# D5035-03.net
KiCad netlist of a schematic drawn in Altium Designer
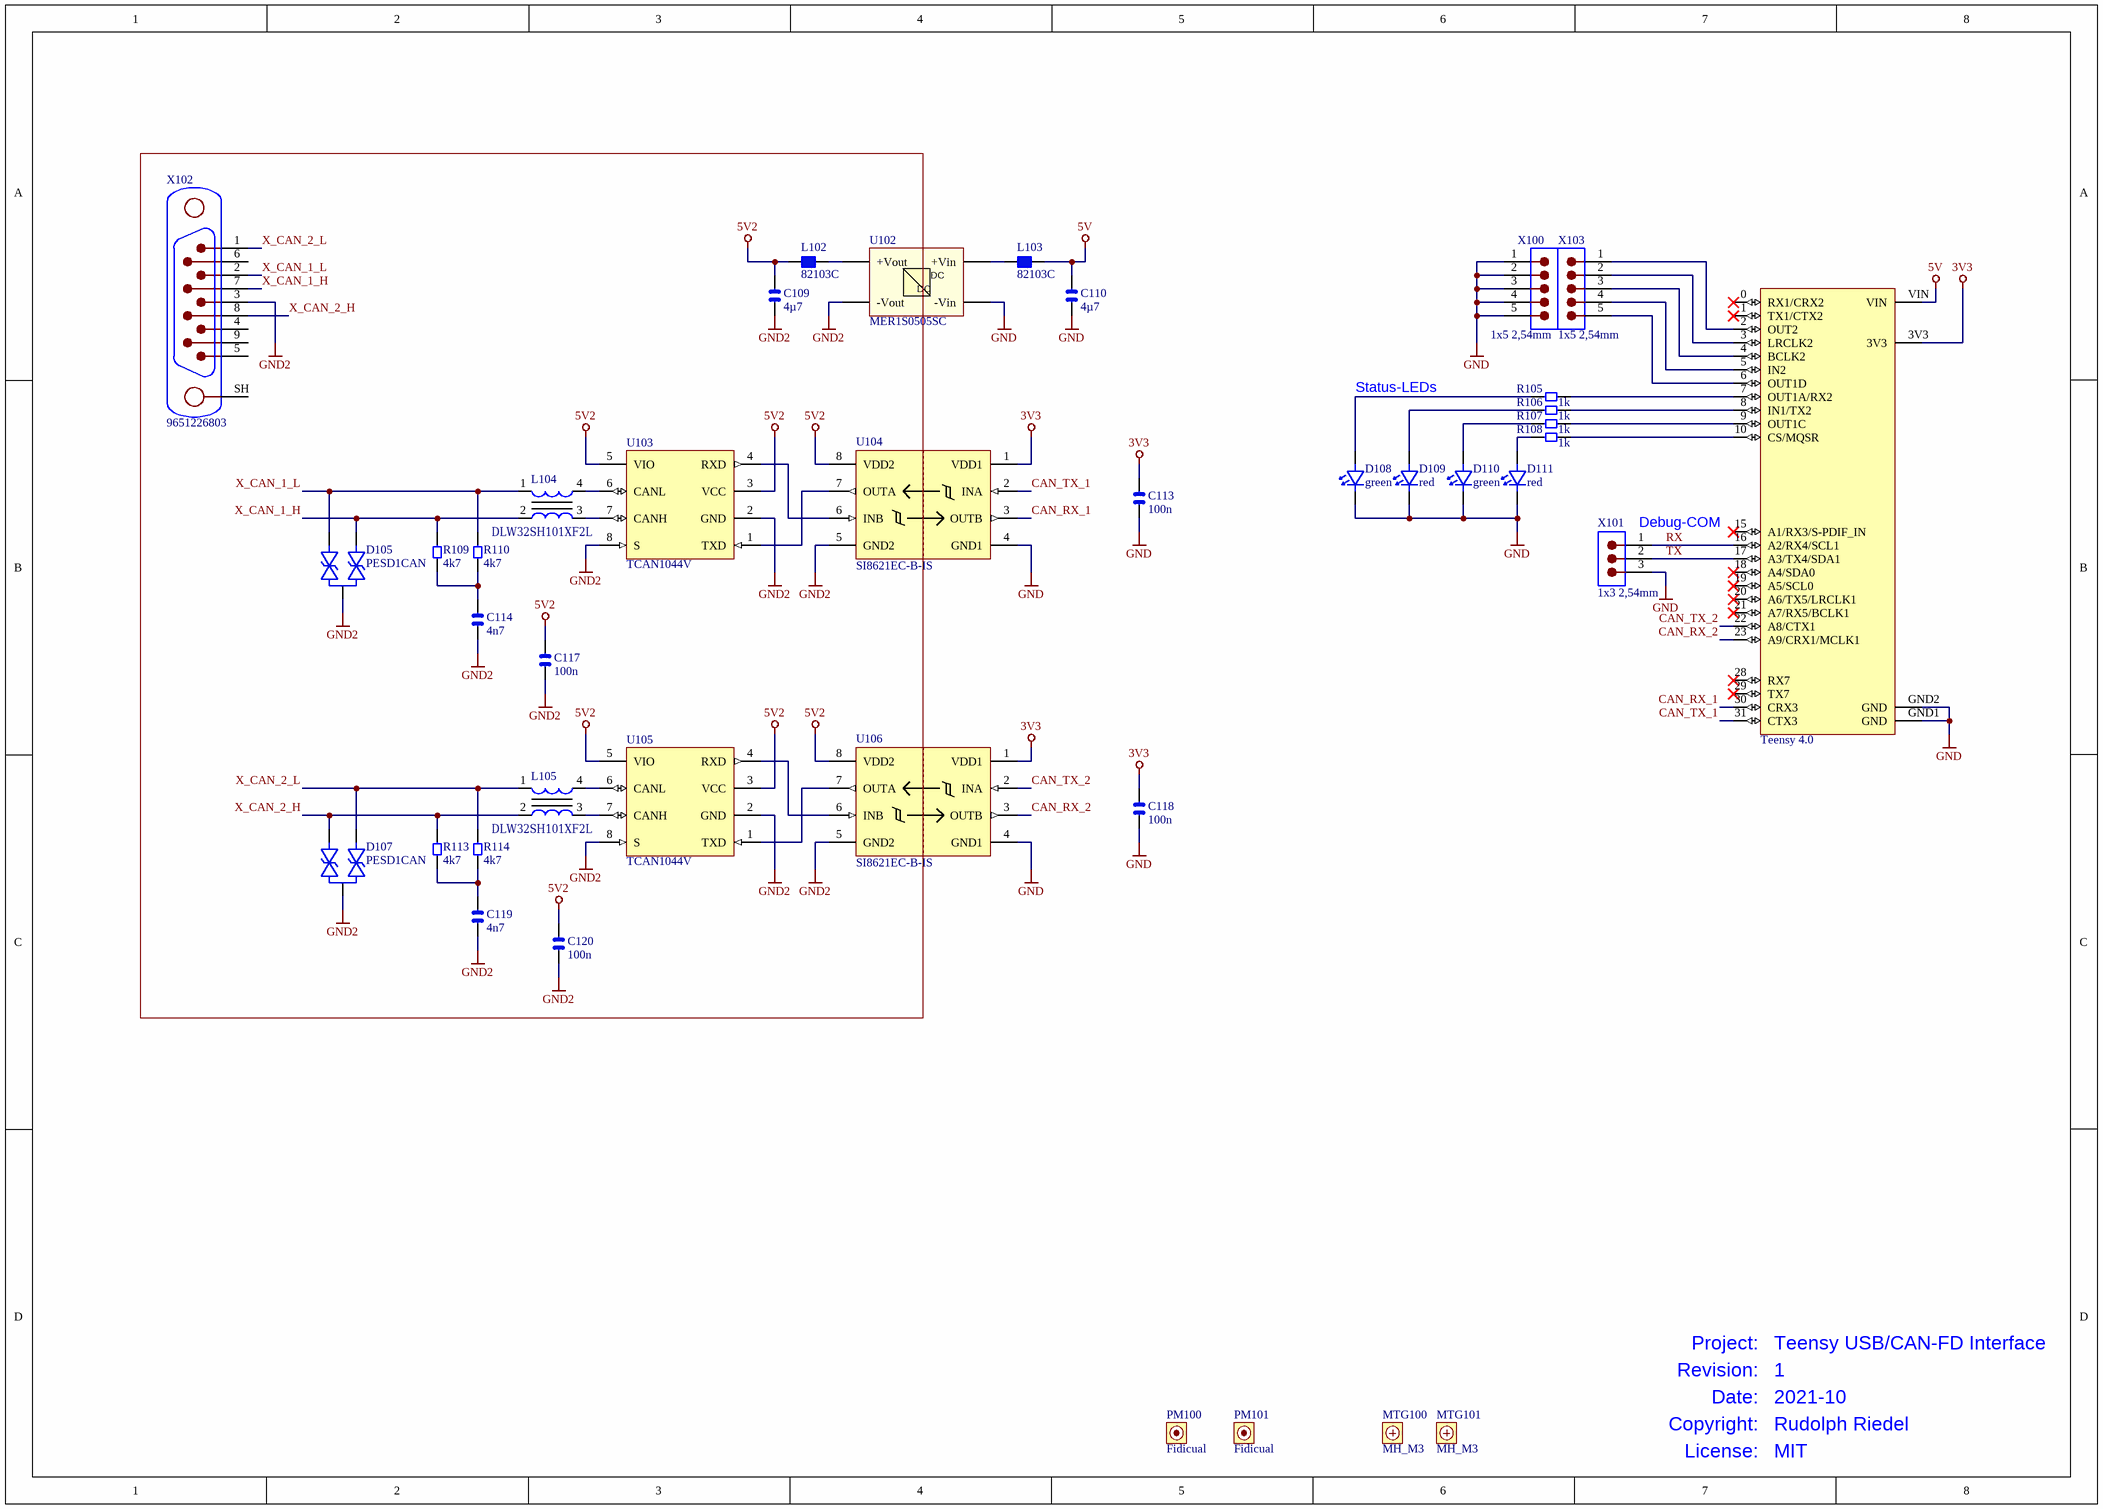
[diagram p0: D5035-03.SchDoc]

(export (version "E")
  (design (tool "Eeschema 10.0.6"))
  (components
    (comp (ref "C109")
      (value "4µ7")
      (footprint "CAPC2012X14L")
      (description "0805 Chip Capacitor")
      (fields (field (name "PART NUMBER") "CAPC_0805") (field (name "EDITOR") "rriedel"))
      (libsource (lib "HW-Labor_GF") (part "CAP_2_V2"))
    )
    (comp (ref "C110")
      (value "4µ7")
      (footprint "CAPC2012X14L")
      (description "0805 Chip Capacitor")
      (fields (field (name "PART NUMBER") "CAPC_0805") (field (name "EDITOR") "rriedel"))
      (libsource (lib "HW-Labor_GF") (part "CAP_2_V2"))
    )
    (comp (ref "C113")
      (value "100n")
      (footprint "CAPC1608X09L")
      (description "0603 Chip Capacitor")
      (fields (field (name "PART NUMBER") "CAPC_0603") (field (name "EDITOR") "rriedel"))
      (libsource (lib "HW-Labor_GF") (part "CAP_2_V2"))
    )
    (comp (ref "C114")
      (value "4n7")
      (footprint "CAPC2012X14L")
      (description "0805 Chip Capacitor")
      (fields (field (name "PART NUMBER") "CAPC_0805") (field (name "EDITOR") "rriedel"))
      (libsource (lib "HW-Labor_GF") (part "CAP_2_V2"))
    )
    (comp (ref "C117")
      (value "100n")
      (footprint "CAPC1608X09L")
      (description "0603 Chip Capacitor")
      (fields (field (name "PART NUMBER") "CAPC_0603") (field (name "EDITOR") "rriedel"))
      (libsource (lib "HW-Labor_GF") (part "CAP_2_V2"))
    )
    (comp (ref "C118")
      (value "100n")
      (footprint "CAPC1608X09L")
      (description "0603 Chip Capacitor")
      (fields (field (name "PART NUMBER") "CAPC_0603") (field (name "EDITOR") "rriedel"))
      (libsource (lib "HW-Labor_GF") (part "CAP_2_V2"))
    )
    (comp (ref "C119")
      (value "4n7")
      (footprint "CAPC2012X14L")
      (description "0805 Chip Capacitor")
      (fields (field (name "PART NUMBER") "CAPC_0805") (field (name "EDITOR") "rriedel"))
      (libsource (lib "HW-Labor_GF") (part "CAP_2_V2"))
    )
    (comp (ref "C120")
      (value "100n")
      (footprint "CAPC1608X09L")
      (description "0603 Chip Capacitor")
      (fields (field (name "PART NUMBER") "CAPC_0603") (field (name "EDITOR") "rriedel"))
      (libsource (lib "HW-Labor_GF") (part "CAP_2_V2"))
    )
    (comp (ref "D105")
      (value "PESD1CAN")
      (footprint "SOT95P280X110-3N")
      (description "CAN bus ESD protection diode")
      (fields
        (field (name "MANUFACTURER") "Nexperia")
        (field (name "DISTRIBUTOR_1_PART_NUMBER") "1727-3817-1-ND")
        (field (name "EDITOR") "rriedel")
      )
      (libsource (lib "HW-Labor_GF") (part "PESD1CAN"))
    )
    (comp (ref "D107")
      (value "PESD1CAN")
      (footprint "SOT95P280X110-3N")
      (description "CAN bus ESD protection diode")
      (fields
        (field (name "MANUFACTURER") "Nexperia")
        (field (name "DISTRIBUTOR_1_PART_NUMBER") "1727-3817-1-ND")
        (field (name "EDITOR") "rriedel")
      )
      (libsource (lib "HW-Labor_GF") (part "PESD1CAN"))
    )
    (comp (ref "D108")
      (value "green")
      (footprint "DIOC1608X06N_LED")
      (description "LED, 0603")
      (fields (field (name "PART NUMBER") "LED_0603") (field (name "EDITOR") "rriedel"))
      (libsource (lib "HW-Labor_GF") (part "LED_generic"))
    )
    (comp (ref "D109")
      (value "red")
      (footprint "DIOC1608X06N_LED")
      (description "LED, 0603")
      (fields (field (name "PART NUMBER") "LED_0603") (field (name "EDITOR") "rriedel"))
      (libsource (lib "HW-Labor_GF") (part "LED_generic"))
    )
    (comp (ref "D110")
      (value "green")
      (footprint "DIOC1608X06N_LED")
      (description "LED, 0603")
      (fields (field (name "PART NUMBER") "LED_0603") (field (name "EDITOR") "rriedel"))
      (libsource (lib "HW-Labor_GF") (part "LED_generic"))
    )
    (comp (ref "D111")
      (value "red")
      (footprint "DIOC1608X06N_LED")
      (description "LED, 0603")
      (fields (field (name "PART NUMBER") "LED_0603") (field (name "EDITOR") "rriedel"))
      (libsource (lib "HW-Labor_GF") (part "LED_generic"))
    )
    (comp (ref "L102")
      (value "82103C")
      (footprint "Murata_8200C")
      (description "10µH, 0,5A, 400mR")
      (fields
        (field (name "MANUFACTURER") "Murata")
        (field (name "DISTRIBUTOR_1_PART_NUMBER") "811-2473-1-ND")
        (field (name "EDITOR") "rriedel")
      )
      (libsource (lib "HW-Labor_GF") (part "IND_2_V1"))
    )
    (comp (ref "L103")
      (value "82103C")
      (footprint "Murata_8200C")
      (description "10µH, 0,5A, 400mR")
      (fields
        (field (name "MANUFACTURER") "Murata")
        (field (name "DISTRIBUTOR_1_PART_NUMBER") "811-2473-1-ND")
        (field (name "EDITOR") "rriedel")
      )
      (libsource (lib "HW-Labor_GF") (part "IND_2_V1"))
    )
    (comp (ref "L104")
      (value "DLW32SH101XF2L‎")
      (footprint "ACT1210")
      (description "Common Mode Filter,  -50°C ... +150°C, AEC-Q200")
      (fields
        (field (name "PART NUMBER") "ACT1210-101-2P-TL00")
        (field (name "MANUFACTURER") "TDK")
        (field (name "EDITOR") "rriedel")
      )
      (libsource (lib "HW-Labor_GF") (part "CAN_DROSSEL"))
    )
    (comp (ref "L105")
      (value "DLW32SH101XF2L‎")
      (footprint "ACT1210")
      (description "Common Mode Filter,  -50°C ... +150°C, AEC-Q200")
      (fields
        (field (name "PART NUMBER") "ACT1210-101-2P-TL00")
        (field (name "MANUFACTURER") "TDK")
        (field (name "EDITOR") "rriedel")
      )
      (libsource (lib "HW-Labor_GF") (part "CAN_DROSSEL"))
    )
    (comp (ref "MTG100")
      (value "MH_M3")
      (footprint "HOLE_3_2MM")
      (description "Mounting-Hole for M3 screws")
      (fields (field (name "EDITOR") "rriedel"))
      (libsource (lib "HW-Labor_GF") (part "MTG_V1"))
    )
    (comp (ref "MTG101")
      (value "MH_M3")
      (footprint "HOLE_3_2MM")
      (description "Mounting-Hole for M3 screws")
      (fields (field (name "EDITOR") "rriedel"))
      (libsource (lib "HW-Labor_GF") (part "MTG_V1"))
    )
    (comp (ref "PM100")
      (value "Fidicual")
      (footprint "PM100")
      (fields (field (name "PART NUMBER") "PM100") (field (name "EDITOR") "rriedel"))
      (libsource (lib "HW-Labor_GF") (part "PM100"))
    )
    (comp (ref "PM101")
      (value "Fidicual")
      (footprint "PM100")
      (fields (field (name "PART NUMBER") "PM100") (field (name "EDITOR") "rriedel"))
      (libsource (lib "HW-Labor_GF") (part "PM100"))
    )
    (comp (ref "R105")
      (value "1k")
      (footprint "RESC1608X06L")
      (description "0603 Chip Resistor")
      (fields (field (name "PART NUMBER") "RESC_0603") (field (name "EDITOR") "rriedel"))
      (libsource (lib "HW-Labor_GF") (part "RES_2_V2"))
    )
    (comp (ref "R106")
      (value "1k")
      (footprint "RESC1608X06L")
      (description "0603 Chip Resistor")
      (fields (field (name "PART NUMBER") "RESC_0603") (field (name "EDITOR") "rriedel"))
      (libsource (lib "HW-Labor_GF") (part "RES_2_V2"))
    )
    (comp (ref "R107")
      (value "1k")
      (footprint "RESC1608X06L")
      (description "0603 Chip Resistor")
      (fields (field (name "PART NUMBER") "RESC_0603") (field (name "EDITOR") "rriedel"))
      (libsource (lib "HW-Labor_GF") (part "RES_2_V2"))
    )
    (comp (ref "R108")
      (value "1k")
      (footprint "RESC1608X06L")
      (description "0603 Chip Resistor")
      (fields (field (name "PART NUMBER") "RESC_0603") (field (name "EDITOR") "rriedel"))
      (libsource (lib "HW-Labor_GF") (part "RES_2_V2"))
    )
    (comp (ref "R109")
      (value "4k7")
      (footprint "RESC2012X06L")
      (description "0805 Chip Resistor")
      (fields (field (name "PART NUMBER") "RESC_0805") (field (name "EDITOR") "rriedel"))
      (libsource (lib "HW-Labor_GF") (part "RES_2_V2"))
    )
    (comp (ref "R110")
      (value "4k7")
      (footprint "RESC2012X06L")
      (description "0805 Chip Resistor")
      (fields (field (name "PART NUMBER") "RESC_0805") (field (name "EDITOR") "rriedel"))
      (libsource (lib "HW-Labor_GF") (part "RES_2_V2"))
    )
    (comp (ref "R113")
      (value "4k7")
      (footprint "RESC2012X06L")
      (description "0805 Chip Resistor")
      (fields (field (name "PART NUMBER") "RESC_0805") (field (name "EDITOR") "rriedel"))
      (libsource (lib "HW-Labor_GF") (part "RES_2_V2"))
    )
    (comp (ref "R114")
      (value "4k7")
      (footprint "RESC2012X06L")
      (description "0805 Chip Resistor")
      (fields (field (name "PART NUMBER") "RESC_0805") (field (name "EDITOR") "rriedel"))
      (libsource (lib "HW-Labor_GF") (part "RES_2_V2"))
    )
    (comp (ref "Teensy 4.0")
      (value "Teensy_4_0_minimal")
      (footprint "Teensy_4_0_minimal")
      (libsource (lib "Teensy4") (part "Teensy_4_0_minimal"))
    )
    (comp (ref "U102")
      (value "MER1S0505SC")
      (footprint "MER1SxxxxC")
      (description "Isolated 1W Single Output DC-DC Converters 5V/5V 200mA")
      (fields
        (field (name "MANUFACTURER") "Murata")
        (field (name "DISTRIBUTOR_1_PART_NUMBER") "811-2124-5-ND‎")
        (field (name "EDITOR") "rriedel")
      )
      (libsource (lib "HW-Labor_GF") (part "MER1SxxxxC"))
    )
    (comp (ref "U103")
      (value "TCAN1044V")
      (footprint "SOT65P280X100-8N")
      (description "CAN-FD transceiver 8MBit, VIO Pin")
      (fields
        (field (name "MANUFACTURER") "TI")
        (field (name "DISTRIBUTOR_1_PART_NUMBER") "296-TCAN1044VDDFRCT-ND")
        (field (name "EDITOR") "rriedel")
      )
      (libsource (lib "HW-Labor_GF") (part "TJA1051T_3"))
    )
    (comp (ref "U104")
      (value "SI8621EC-B-IS")
      (footprint "SOIC127P600X175-8N")
      (description "Dual channel digital isolator, 150Mbit, 3,75kV")
      (fields
        (field (name "MANUFACTURER") "Silicon Labs")
        (field (name "DISTRIBUTOR_1_PART_NUMBER") "336-4776-1-ND")
        (field (name "EDITOR") "rriedel")
      )
      (libsource (lib "HW-Labor_GF") (part "SI8621"))
    )
    (comp (ref "U105")
      (value "TCAN1044V")
      (footprint "SOT65P280X100-8N")
      (description "CAN-FD transceiver 8MBit, VIO Pin")
      (fields
        (field (name "MANUFACTURER") "TI")
        (field (name "DISTRIBUTOR_1_PART_NUMBER") "296-TCAN1044VDDFRCT-ND")
        (field (name "EDITOR") "rriedel")
      )
      (libsource (lib "HW-Labor_GF") (part "TJA1051T_3"))
    )
    (comp (ref "U106")
      (value "SI8621EC-B-IS")
      (footprint "SOIC127P600X175-8N")
      (description "Dual channel digital isolator, 150Mbit, 3,75kV")
      (fields
        (field (name "MANUFACTURER") "Silicon Labs")
        (field (name "DISTRIBUTOR_1_PART_NUMBER") "336-4776-1-ND")
        (field (name "EDITOR") "rriedel")
      )
      (libsource (lib "HW-Labor_GF") (part "SI8621"))
    )
    (comp (ref "X100")
      (value "1x5 2,54mm")
      (footprint "PAD_1x05_2_54mm")
      (description "Pin-Header 2,54 mm 5pins")
      (fields (field (name "PART NUMBER") "PINH_1x5_2_54") (field (name "EDITOR") "rriedel"))
      (libsource (lib "HW-Labor_GF") (part "CONM_1x5_V2"))
    )
    (comp (ref "X101")
      (value "1x3 2,54mm")
      (footprint "PINH_1x03_2_54mm")
      (description "Pin-Header 2,54 mm 3pins")
      (fields (field (name "PART NUMBER") "PINH_1x3_2_54") (field (name "EDITOR") "rriedel"))
      (libsource (lib "HW-Labor_GF") (part "CONM_1x3_V2"))
    )
    (comp (ref "X102")
      (value "9651226803")
      (footprint "09651226803")
      (description "D-Sub, 9 pin, male, right angle")
      (fields
        (field (name "MANUFACTURER") "Harting")
        (field (name "DISTRIBUTOR_1_PART_NUMBER") "2752007")
        (field (name "EDITOR") "rriedel")
      )
      (libsource (lib "HW-Labor_GF") (part "D_Sub_9_Male"))
    )
    (comp (ref "X103")
      (value "1x5 2,54mm")
      (footprint "PAD_1x05_2_54mm")
      (description "Pin-Header 2,54 mm 5pins")
      (fields (field (name "PART NUMBER") "PINH_1x5_2_54") (field (name "EDITOR") "rriedel"))
      (libsource (lib "HW-Labor_GF") (part "CONM_1x5_V2"))
    )
  )
  (nets
    (net (code "1") (name "/CAN_RX_1") (class "Default")
      (node (ref "Teensy 4.0") (pin "30") (pinfunction "CRX3_30") (pintype "bidirectional"))
      (node (ref "U104") (pin "3") (pinfunction "OUTB_3") (pintype "output"))
    )
    (net (code "2") (name "/CAN_RX_2") (class "Default")
      (node (ref "Teensy 4.0") (pin "23") (pinfunction "A9/CRX1/MCLK1_23") (pintype "bidirectional"))
      (node (ref "U106") (pin "3") (pinfunction "OUTB_3") (pintype "output"))
    )
    (net (code "3") (name "/CAN_TX_1") (class "Default")
      (node (ref "Teensy 4.0") (pin "31") (pinfunction "CTX3_31") (pintype "bidirectional"))
      (node (ref "U104") (pin "2") (pinfunction "INA_2") (pintype "input"))
    )
    (net (code "4") (name "/CAN_TX_2") (class "Default")
      (node (ref "Teensy 4.0") (pin "22") (pinfunction "A8/CTX1_22") (pintype "bidirectional"))
      (node (ref "U106") (pin "2") (pinfunction "INA_2") (pintype "input"))
    )
    (net (code "5") (name "/RX") (class "Default")
      (node (ref "Teensy 4.0") (pin "16") (pinfunction "A2/RX4/SCL1_16") (pintype "bidirectional"))
      (node (ref "X101") (pin "1") (pinfunction "1_1") (pintype "passive"))
    )
    (net (code "6") (name "/TX") (class "Default")
      (node (ref "Teensy 4.0") (pin "17") (pinfunction "A3/TX4/SDA1_17") (pintype "bidirectional"))
      (node (ref "X101") (pin "2") (pinfunction "2_2") (pintype "passive"))
    )
    (net (code "7") (name "/X_CAN_1_H") (class "Default")
      (node (ref "D105") (pin "2") (pinfunction "2_2") (pintype "passive"))
      (node (ref "L104") (pin "2") (pintype "passive"))
      (node (ref "R109") (pin "2") (pinfunction "2_2") (pintype "passive"))
      (node (ref "X102") (pin "7") (pinfunction "7_7") (pintype "passive"))
    )
    (net (code "8") (name "/X_CAN_1_L") (class "Default")
      (node (ref "D105") (pin "1") (pinfunction "1_1") (pintype "passive"))
      (node (ref "L104") (pin "1") (pintype "passive"))
      (node (ref "R110") (pin "2") (pinfunction "2_2") (pintype "passive"))
      (node (ref "X102") (pin "2") (pinfunction "2_2") (pintype "passive"))
    )
    (net (code "9") (name "/X_CAN_2_H") (class "Default")
      (node (ref "D107") (pin "1") (pinfunction "1_1") (pintype "passive"))
      (node (ref "L105") (pin "2") (pintype "passive"))
      (node (ref "R113") (pin "2") (pinfunction "2_2") (pintype "passive"))
      (node (ref "X102") (pin "8") (pinfunction "8_8") (pintype "passive"))
    )
    (net (code "10") (name "/X_CAN_2_L") (class "Default")
      (node (ref "D107") (pin "2") (pinfunction "2_2") (pintype "passive"))
      (node (ref "L105") (pin "1") (pintype "passive"))
      (node (ref "R114") (pin "2") (pinfunction "2_2") (pintype "passive"))
      (node (ref "X102") (pin "1") (pinfunction "1_1") (pintype "passive"))
    )
    (net (code "11") (name "3V3") (class "Default")
      (node (ref "C113") (pin "2") (pinfunction "2_2") (pintype "passive"))
      (node (ref "C118") (pin "2") (pinfunction "2_2") (pintype "passive"))
      (node (ref "Teensy 4.0") (pin "3V3") (pinfunction "3V3_3V3") (pintype "power_in"))
      (node (ref "U104") (pin "1") (pinfunction "VDD1_1") (pintype "power_in"))
      (node (ref "U106") (pin "1") (pinfunction "VDD1_1") (pintype "power_in"))
    )
    (net (code "12") (name "5V") (class "Default")
      (node (ref "C110") (pin "2") (pinfunction "2_2") (pintype "passive"))
      (node (ref "L103") (pin "1") (pinfunction "1_1") (pintype "passive"))
      (node (ref "Teensy 4.0") (pin "VIN") (pinfunction "VIN_VIN") (pintype "power_in"))
    )
    (net (code "13") (name "5V2") (class "Default")
      (node (ref "C109") (pin "2") (pinfunction "2_2") (pintype "passive"))
      (node (ref "C117") (pin "2") (pinfunction "2_2") (pintype "passive"))
      (node (ref "C120") (pin "2") (pinfunction "2_2") (pintype "passive"))
      (node (ref "L102") (pin "2") (pinfunction "2_2") (pintype "passive"))
      (node (ref "U103") (pin "3") (pinfunction "VCC_3") (pintype "power_in"))
      (node (ref "U103") (pin "5") (pinfunction "VIO_5") (pintype "power_in"))
      (node (ref "U104") (pin "8") (pinfunction "VDD2_8") (pintype "power_in"))
      (node (ref "U105") (pin "3") (pinfunction "VCC_3") (pintype "power_in"))
      (node (ref "U105") (pin "5") (pinfunction "VIO_5") (pintype "power_in"))
      (node (ref "U106") (pin "8") (pinfunction "VDD2_8") (pintype "power_in"))
    )
    (net (code "14") (name "GND") (class "Default")
      (node (ref "C110") (pin "1") (pinfunction "1_1") (pintype "passive"))
      (node (ref "C113") (pin "1") (pinfunction "1_1") (pintype "passive"))
      (node (ref "C118") (pin "1") (pinfunction "1_1") (pintype "passive"))
      (node (ref "D108") (pin "1") (pinfunction "1_1") (pintype "passive"))
      (node (ref "D109") (pin "1") (pinfunction "1_1") (pintype "passive"))
      (node (ref "D110") (pin "1") (pinfunction "1_1") (pintype "passive"))
      (node (ref "D111") (pin "1") (pinfunction "1_1") (pintype "passive"))
      (node (ref "Teensy 4.0") (pin "GND1") (pinfunction "GND_GND1") (pintype "power_in"))
      (node (ref "Teensy 4.0") (pin "GND2") (pinfunction "GND_GND2") (pintype "power_in"))
      (node (ref "U102") (pin "2") (pinfunction "-Vin_2") (pintype "power_in"))
      (node (ref "U104") (pin "4") (pinfunction "GND1_4") (pintype "power_in"))
      (node (ref "U106") (pin "4") (pinfunction "GND1_4") (pintype "power_in"))
      (node (ref "X100") (pin "1") (pinfunction "1_1") (pintype "passive"))
      (node (ref "X100") (pin "2") (pinfunction "2_2") (pintype "passive"))
      (node (ref "X100") (pin "3") (pinfunction "3_3") (pintype "passive"))
      (node (ref "X100") (pin "4") (pinfunction "4_4") (pintype "passive"))
      (node (ref "X100") (pin "5") (pinfunction "5_5") (pintype "passive"))
      (node (ref "X101") (pin "3") (pinfunction "3_3") (pintype "passive"))
    )
    (net (code "15") (name "GND2") (class "Default")
      (node (ref "C109") (pin "1") (pinfunction "1_1") (pintype "passive"))
      (node (ref "C114") (pin "1") (pinfunction "1_1") (pintype "passive"))
      (node (ref "C117") (pin "1") (pinfunction "1_1") (pintype "passive"))
      (node (ref "C119") (pin "1") (pinfunction "1_1") (pintype "passive"))
      (node (ref "C120") (pin "1") (pinfunction "1_1") (pintype "passive"))
      (node (ref "D105") (pin "3") (pinfunction "3_3") (pintype "passive"))
      (node (ref "D107") (pin "3") (pinfunction "3_3") (pintype "passive"))
      (node (ref "U102") (pin "4") (pinfunction "-Vout_4") (pintype "power_in"))
      (node (ref "U103") (pin "2") (pinfunction "GND_2") (pintype "power_in"))
      (node (ref "U103") (pin "8") (pinfunction "S_8") (pintype "input"))
      (node (ref "U104") (pin "5") (pinfunction "GND2_5") (pintype "power_in"))
      (node (ref "U105") (pin "2") (pinfunction "GND_2") (pintype "power_in"))
      (node (ref "U105") (pin "8") (pinfunction "S_8") (pintype "input"))
      (node (ref "U106") (pin "5") (pinfunction "GND2_5") (pintype "power_in"))
      (node (ref "X102") (pin "3") (pinfunction "3_3") (pintype "passive"))
    )
    (net (code "16") (name "Net-(C114-Pad2)") (class "Default")
      (node (ref "C114") (pin "2") (pinfunction "2_2") (pintype "passive"))
      (node (ref "R109") (pin "1") (pinfunction "1_1") (pintype "passive"))
      (node (ref "R110") (pin "1") (pinfunction "1_1") (pintype "passive"))
    )
    (net (code "17") (name "Net-(C119-Pad2)") (class "Default")
      (node (ref "C119") (pin "2") (pinfunction "2_2") (pintype "passive"))
      (node (ref "R113") (pin "1") (pinfunction "1_1") (pintype "passive"))
      (node (ref "R114") (pin "1") (pinfunction "1_1") (pintype "passive"))
    )
    (net (code "18") (name "Net-(D108-Pad2)") (class "Default")
      (node (ref "D108") (pin "2") (pinfunction "2_2") (pintype "passive"))
      (node (ref "R105") (pin "1") (pinfunction "1_1") (pintype "passive"))
    )
    (net (code "19") (name "Net-(D109-Pad2)") (class "Default")
      (node (ref "D109") (pin "2") (pinfunction "2_2") (pintype "passive"))
      (node (ref "R106") (pin "1") (pinfunction "1_1") (pintype "passive"))
    )
    (net (code "20") (name "Net-(D110-Pad2)") (class "Default")
      (node (ref "D110") (pin "2") (pinfunction "2_2") (pintype "passive"))
      (node (ref "R107") (pin "1") (pinfunction "1_1") (pintype "passive"))
    )
    (net (code "21") (name "Net-(D111-Pad2)") (class "Default")
      (node (ref "D111") (pin "2") (pinfunction "2_2") (pintype "passive"))
      (node (ref "R108") (pin "1") (pinfunction "1_1") (pintype "passive"))
    )
    (net (code "22") (name "Net-(Teensy 4.0-BCLK2)") (class "Default")
      (node (ref "Teensy 4.0") (pin "4") (pinfunction "BCLK2_4") (pintype "bidirectional"))
      (node (ref "X103") (pin "3") (pinfunction "3_3") (pintype "passive"))
    )
    (net (code "23") (name "Net-(Teensy 4.0-CS{slash}MQSR)") (class "Default")
      (node (ref "R108") (pin "2") (pinfunction "2_2") (pintype "passive"))
      (node (ref "Teensy 4.0") (pin "10") (pinfunction "CS/MQSR_10") (pintype "bidirectional"))
    )
    (net (code "24") (name "Net-(Teensy 4.0-IN1{slash}TX2)") (class "Default")
      (node (ref "R106") (pin "2") (pinfunction "2_2") (pintype "passive"))
      (node (ref "Teensy 4.0") (pin "8") (pinfunction "IN1/TX2_8") (pintype "bidirectional"))
    )
    (net (code "25") (name "Net-(Teensy 4.0-IN2)") (class "Default")
      (node (ref "Teensy 4.0") (pin "5") (pinfunction "IN2_5") (pintype "bidirectional"))
      (node (ref "X103") (pin "4") (pinfunction "4_4") (pintype "passive"))
    )
    (net (code "26") (name "Net-(Teensy 4.0-LRCLK2)") (class "Default")
      (node (ref "Teensy 4.0") (pin "3") (pinfunction "LRCLK2_3") (pintype "bidirectional"))
      (node (ref "X103") (pin "2") (pinfunction "2_2") (pintype "passive"))
    )
    (net (code "27") (name "Net-(Teensy 4.0-OUT1A{slash}RX2)") (class "Default")
      (node (ref "R105") (pin "2") (pinfunction "2_2") (pintype "passive"))
      (node (ref "Teensy 4.0") (pin "7") (pinfunction "OUT1A/RX2_7") (pintype "bidirectional"))
    )
    (net (code "28") (name "Net-(Teensy 4.0-OUT1C)") (class "Default")
      (node (ref "R107") (pin "2") (pinfunction "2_2") (pintype "passive"))
      (node (ref "Teensy 4.0") (pin "9") (pinfunction "OUT1C_9") (pintype "bidirectional"))
    )
    (net (code "29") (name "Net-(Teensy 4.0-OUT1D)") (class "Default")
      (node (ref "Teensy 4.0") (pin "6") (pinfunction "OUT1D_6") (pintype "bidirectional"))
      (node (ref "X103") (pin "5") (pinfunction "5_5") (pintype "passive"))
    )
    (net (code "30") (name "Net-(Teensy 4.0-OUT2)") (class "Default")
      (node (ref "Teensy 4.0") (pin "2") (pinfunction "OUT2_2") (pintype "bidirectional"))
      (node (ref "X103") (pin "1") (pinfunction "1_1") (pintype "passive"))
    )
    (net (code "31") (name "Net-(U102-+Vin)") (class "Default")
      (node (ref "L103") (pin "2") (pinfunction "2_2") (pintype "passive"))
      (node (ref "U102") (pin "1") (pinfunction "+Vin_1") (pintype "power_in"))
    )
    (net (code "32") (name "Net-(U102-+Vout)") (class "Default")
      (node (ref "L102") (pin "1") (pinfunction "1_1") (pintype "passive"))
      (node (ref "U102") (pin "6") (pinfunction "+Vout_6") (pintype "power_in"))
    )
    (net (code "33") (name "Net-(U103-CANH)") (class "Default")
      (node (ref "L104") (pin "3") (pintype "passive"))
      (node (ref "U103") (pin "7") (pinfunction "CANH_7") (pintype "bidirectional"))
    )
    (net (code "34") (name "Net-(U103-CANL)") (class "Default")
      (node (ref "L104") (pin "4") (pintype "passive"))
      (node (ref "U103") (pin "6") (pinfunction "CANL_6") (pintype "bidirectional"))
    )
    (net (code "35") (name "Net-(U103-RXD)") (class "Default")
      (node (ref "U103") (pin "4") (pinfunction "RXD_4") (pintype "output"))
      (node (ref "U104") (pin "6") (pinfunction "INB_6") (pintype "input"))
    )
    (net (code "36") (name "Net-(U103-TXD)") (class "Default")
      (node (ref "U103") (pin "1") (pinfunction "TXD_1") (pintype "input"))
      (node (ref "U104") (pin "7") (pinfunction "OUTA_7") (pintype "output"))
    )
    (net (code "37") (name "Net-(U105-CANH)") (class "Default")
      (node (ref "L105") (pin "3") (pintype "passive"))
      (node (ref "U105") (pin "7") (pinfunction "CANH_7") (pintype "bidirectional"))
    )
    (net (code "38") (name "Net-(U105-CANL)") (class "Default")
      (node (ref "L105") (pin "4") (pintype "passive"))
      (node (ref "U105") (pin "6") (pinfunction "CANL_6") (pintype "bidirectional"))
    )
    (net (code "39") (name "Net-(U105-RXD)") (class "Default")
      (node (ref "U105") (pin "4") (pinfunction "RXD_4") (pintype "output"))
      (node (ref "U106") (pin "6") (pinfunction "INB_6") (pintype "input"))
    )
    (net (code "40") (name "Net-(U105-TXD)") (class "Default")
      (node (ref "U105") (pin "1") (pinfunction "TXD_1") (pintype "input"))
      (node (ref "U106") (pin "7") (pinfunction "OUTA_7") (pintype "output"))
    )
    (net (code "41") (name "unconnected-(Teensy 4.0-A1{slash}RX3{slash}S-PDIF_IN-Pad15)") (class "Default")
      (node (ref "Teensy 4.0") (pin "15") (pinfunction "A1/RX3/S-PDIF_IN_15") (pintype "bidirectional+no_connect"))
    )
    (net (code "42") (name "unconnected-(Teensy 4.0-A4{slash}SDA0-Pad18)") (class "Default")
      (node (ref "Teensy 4.0") (pin "18") (pinfunction "A4/SDA0_18") (pintype "bidirectional+no_connect"))
    )
    (net (code "43") (name "unconnected-(Teensy 4.0-A5{slash}SCL0-Pad19)") (class "Default")
      (node (ref "Teensy 4.0") (pin "19") (pinfunction "A5/SCL0_19") (pintype "bidirectional+no_connect"))
    )
    (net (code "44") (name "unconnected-(Teensy 4.0-A6{slash}TX5{slash}LRCLK1-Pad20)") (class "Default")
      (node (ref "Teensy 4.0") (pin "20") (pinfunction "A6/TX5/LRCLK1_20") (pintype "bidirectional+no_connect"))
    )
    (net (code "45") (name "unconnected-(Teensy 4.0-A7{slash}RX5{slash}BCLK1-Pad21)") (class "Default")
      (node (ref "Teensy 4.0") (pin "21") (pinfunction "A7/RX5/BCLK1_21") (pintype "bidirectional+no_connect"))
    )
    (net (code "46") (name "unconnected-(Teensy 4.0-RX1{slash}CRX2-Pad0)") (class "Default")
      (node (ref "Teensy 4.0") (pin "0") (pinfunction "RX1/CRX2_0") (pintype "bidirectional+no_connect"))
    )
    (net (code "47") (name "unconnected-(Teensy 4.0-RX7-Pad28)") (class "Default")
      (node (ref "Teensy 4.0") (pin "28") (pinfunction "RX7_28") (pintype "bidirectional+no_connect"))
    )
    (net (code "48") (name "unconnected-(Teensy 4.0-TX1{slash}CTX2-Pad1)") (class "Default")
      (node (ref "Teensy 4.0") (pin "1") (pinfunction "TX1/CTX2_1") (pintype "bidirectional+no_connect"))
    )
    (net (code "49") (name "unconnected-(Teensy 4.0-TX7-Pad29)") (class "Default")
      (node (ref "Teensy 4.0") (pin "29") (pinfunction "TX7_29") (pintype "bidirectional+no_connect"))
    )
    (net (code "50") (name "unconnected-(X102-Pad4)") (class "Default")
      (node (ref "X102") (pin "4") (pinfunction "4_4") (pintype "passive"))
    )
    (net (code "51") (name "unconnected-(X102-Pad5)") (class "Default")
      (node (ref "X102") (pin "5") (pinfunction "5_5") (pintype "passive"))
    )
    (net (code "52") (name "unconnected-(X102-Pad6)") (class "Default")
      (node (ref "X102") (pin "6") (pinfunction "6_6") (pintype "passive"))
    )
    (net (code "53") (name "unconnected-(X102-Pad9)") (class "Default")
      (node (ref "X102") (pin "9") (pinfunction "9_9") (pintype "passive"))
    )
    (net (code "54") (name "unconnected-(X102-PadSH)") (class "Default")
      (node (ref "X102") (pin "SH") (pinfunction "SH_SH") (pintype "passive"))
    )
  )
)
